# AS726x_Breakout.net
KiCad netlist of a schematic drawn in EAGLE
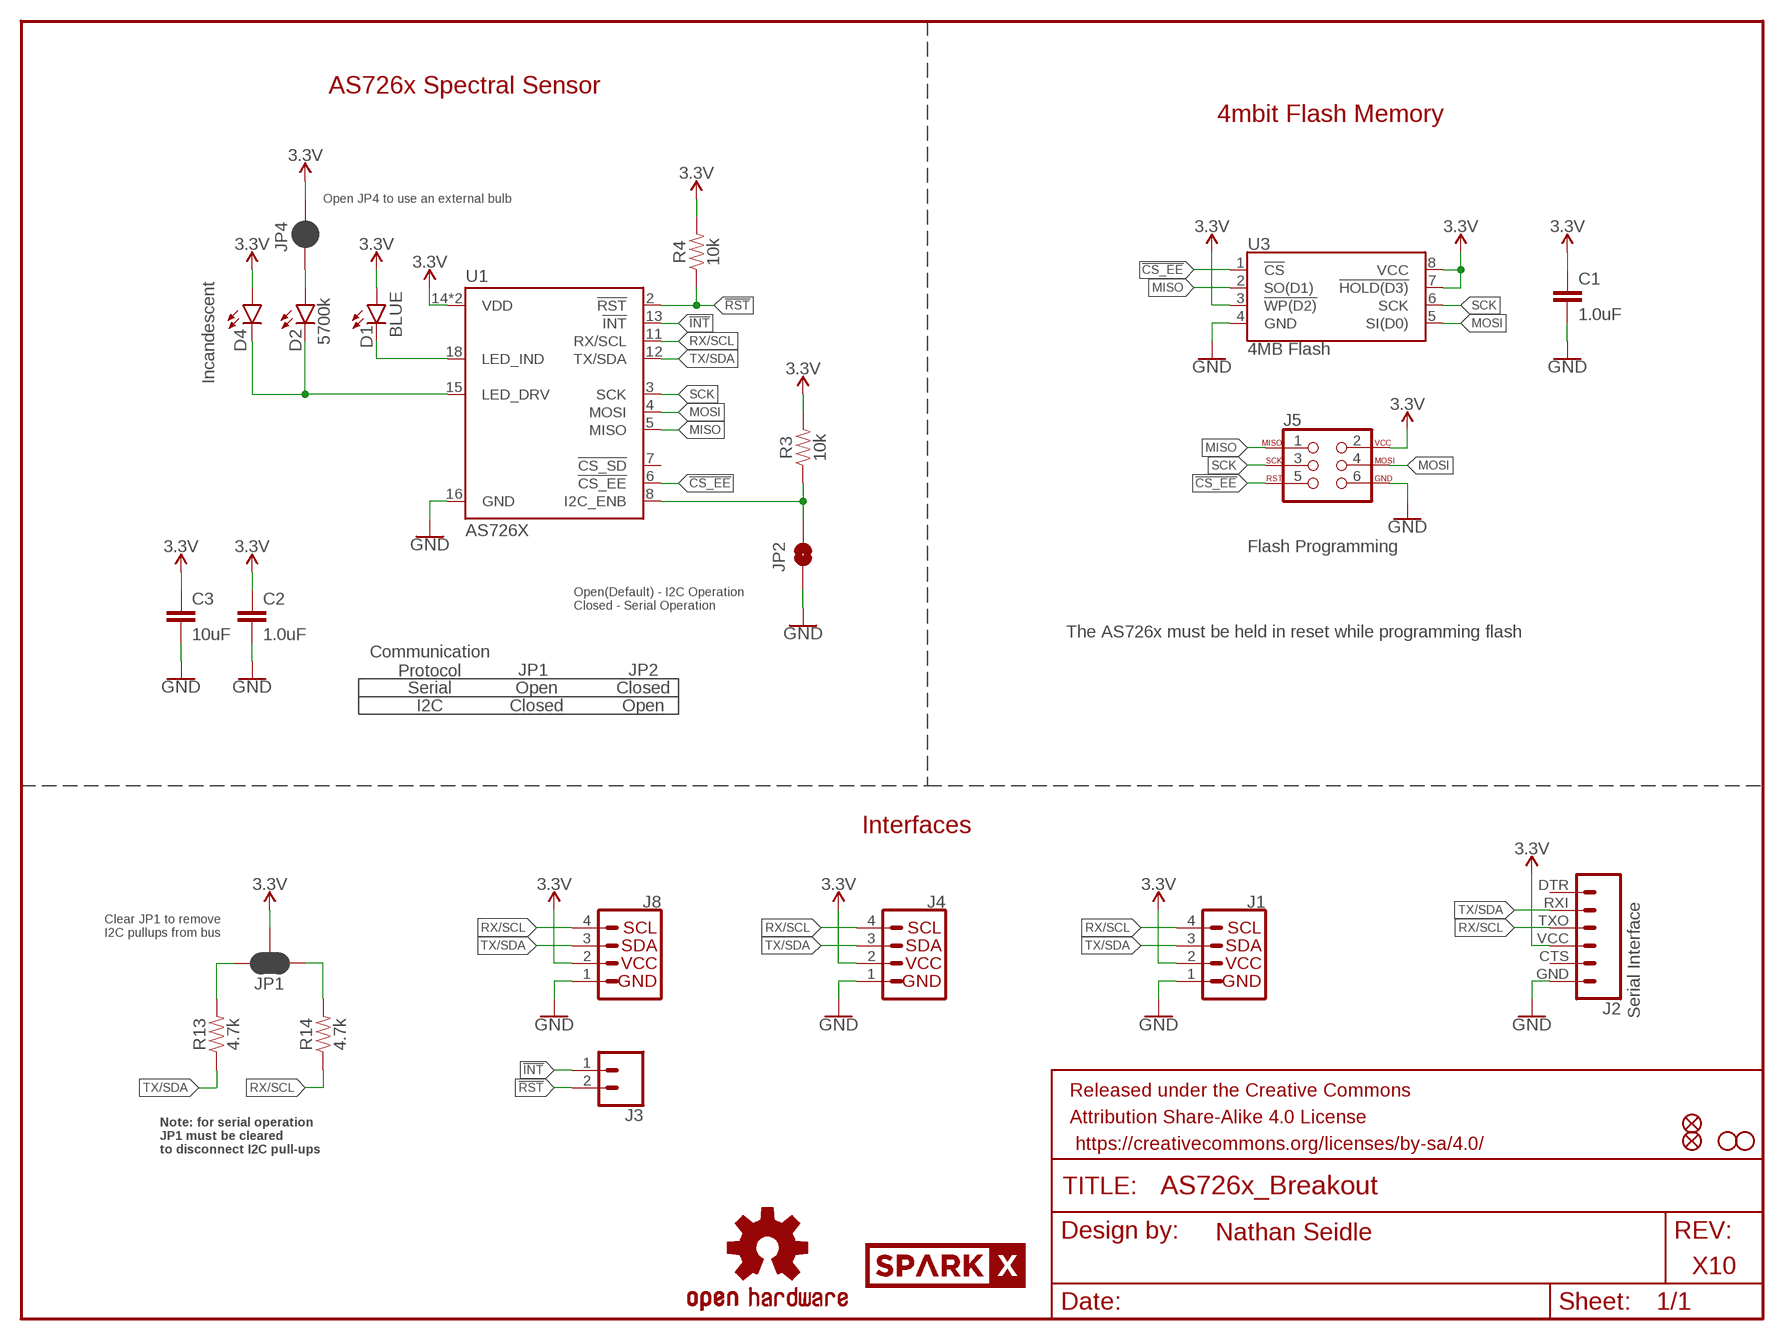
[diagram p0: schematic, sheet 1]

(export (version "E")
  (design (tool "Eeschema 10.0.6"))
  (components
    (comp (ref "C1")
      (value "1.0uF")
      (footprint "eagle-import:0603")
      (libsource (lib "eagle-import") (part "1.0UF-0603-16V-10%"))
    )
    (comp (ref "C2")
      (value "1.0uF")
      (footprint "eagle-import:0603")
      (libsource (lib "eagle-import") (part "1.0UF-0603-16V-10%"))
    )
    (comp (ref "C3")
      (value "10uF")
      (footprint "eagle-import:0603")
      (libsource (lib "eagle-import") (part "10UF-0603-6.3V-20%"))
    )
    (comp (ref "D1")
      (value "BLUE")
      (footprint "eagle-import:LED-0603")
      (libsource (lib "eagle-import") (part "LED-BLUE0603"))
    )
    (comp (ref "D2")
      (value "5700k")
      (footprint "eagle-import:SUPER_BRIGHT_SMD_LED_1206")
      (libsource (lib "eagle-import") (part "LEDLD"))
    )
    (comp (ref "D4")
      (value "Incandescent")
      (footprint "eagle-import:LED_5MM_NOSILK")
      (libsource (lib "eagle-import") (part "LEDNS"))
    )
    (comp (ref "FD1")
      (value "FIDUCIAL1X2")
      (footprint "eagle-import:FIDUCIAL-1X2")
      (libsource (lib "eagle-import") (part "FIDUCIAL1X2"))
    )
    (comp (ref "FD2")
      (value "FIDUCIAL1X2")
      (footprint "eagle-import:FIDUCIAL-1X2")
      (libsource (lib "eagle-import") (part "FIDUCIAL1X2"))
    )
    (comp (ref "FRAME1")
      (value "FRAME-LETTER")
      (footprint "eagle-import:CREATIVE_COMMONS")
      (libsource (lib "eagle-import") (part "FRAME-LETTER"))
    )
    (comp (ref "H2")
      (value "STAND-OFF")
      (footprint "eagle-import:STAND-OFF")
      (libsource (lib "eagle-import") (part "STAND-OFF"))
    )
    (comp (ref "H4")
      (value "STAND-OFF")
      (footprint "eagle-import:STAND-OFF")
      (libsource (lib "eagle-import") (part "STAND-OFF"))
    )
    (comp (ref "J1")
      (value "I2C_STANDARDJS-1MM")
      (footprint "eagle-import:1X04_1MM_RA")
      (libsource (lib "eagle-import") (part "I2C_STANDARDJS-1MM"))
    )
    (comp (ref "J2")
      (value "Serial Interface")
      (footprint "eagle-import:FTDI_BASIC")
      (libsource (lib "eagle-import") (part "6_PIN_SERIAL_CABLEPTH"))
    )
    (comp (ref "J3")
      (value "CONN_021X02_NO_SILK")
      (footprint "eagle-import:1X02_NO_SILK")
      (libsource (lib "eagle-import") (part "CONN_021X02_NO_SILK"))
    )
    (comp (ref "J4")
      (value "I2C_STANDARDJS-1MM")
      (footprint "eagle-import:1X04_1MM_RA")
      (libsource (lib "eagle-import") (part "I2C_STANDARDJS-1MM"))
    )
    (comp (ref "J5")
      (value "Flash Programming")
      (footprint "eagle-import:2X3_TEST_POINTS")
      (libsource (lib "eagle-import") (part "AVR_SPI_PROG_3X2TESTPOINTS"))
    )
    (comp (ref "J8")
      (value "I2C_STANDARD_NO_SILK")
      (footprint "eagle-import:1X04_NO_SILK")
      (libsource (lib "eagle-import") (part "I2C_STANDARD_NO_SILK"))
    )
    (comp (ref "JP1")
      (value "JUMPER-SMT_3_2-NC_PASTE_SILK")
      (footprint "eagle-import:SMT-JUMPER_3_2-NC_PASTE_SILK")
      (libsource (lib "eagle-import") (part "JUMPER-SMT_3_2-NC_PASTE_SILK"))
    )
    (comp (ref "JP2")
      (value "JUMPER-SMT_2_NO_SILK")
      (footprint "eagle-import:SMT-JUMPER_2_NO_SILK")
      (libsource (lib "eagle-import") (part "JUMPER-SMT_2_NO_SILK"))
    )
    (comp (ref "JP4")
      (value "JUMPER-SMT_2_NC_PASTE_NO-SILK")
      (footprint "eagle-import:SMT-JUMPER_2_NC_PASTE_NO-SILK")
      (libsource (lib "eagle-import") (part "JUMPER-SMT_2_NC_PASTE_NO-SILK"))
    )
    (comp (ref "LOGO4")
      (value "OSHW-LOGOS")
      (footprint "eagle-import:OSHW-LOGO-S")
      (libsource (lib "eagle-import") (part "OSHW-LOGOS"))
    )
    (comp (ref "R3")
      (value "10k")
      (footprint "eagle-import:0603")
      (libsource (lib "eagle-import") (part "10KOHM-0603-1/10W-1%"))
    )
    (comp (ref "R4")
      (value "10k")
      (footprint "eagle-import:0603")
      (libsource (lib "eagle-import") (part "10KOHM-0603-1/10W-1%"))
    )
    (comp (ref "R13")
      (value "4.7k")
      (footprint "eagle-import:0603")
      (libsource (lib "eagle-import") (part "4.7KOHM-0603-1/10W-1%"))
    )
    (comp (ref "R14")
      (value "4.7k")
      (footprint "eagle-import:0603")
      (libsource (lib "eagle-import") (part "4.7KOHM-0603-1/10W-1%"))
    )
    (comp (ref "U$1")
      (value "SPARKX-LOGO3")
      (footprint "eagle-import:SPARKX-SMALL")
      (libsource (lib "eagle-import") (part "SPARKX-LOGO3"))
    )
    (comp (ref "U1")
      (value "AS726X")
      (footprint "eagle-import:LGA20")
      (libsource (lib "eagle-import") (part "AS726X"))
    )
    (comp (ref "U3")
      (value "4MB Flash")
      (footprint "eagle-import:SO08")
      (libsource (lib "eagle-import") (part "AT25SF041"))
    )
  )
  (nets
    (net (code "1") (name "/~{CS_EE}") (class "Default")
      (node (ref "J5") (pin "5") (pinfunction "5_5") (pintype "passive"))
      (node (ref "U1") (pin "6") (pinfunction "~{CS_EE}_6") (pintype "bidirectional"))
      (node (ref "U3") (pin "1") (pinfunction "~{CS}_1") (pintype "bidirectional"))
    )
    (net (code "2") (name "/~{INT}") (class "Default")
      (node (ref "J3") (pin "1") (pinfunction "1_1") (pintype "passive"))
      (node (ref "U1") (pin "13") (pinfunction "~{INT}_13") (pintype "bidirectional"))
    )
    (net (code "3") (name "/~{RST}") (class "Default")
      (node (ref "J3") (pin "2") (pinfunction "2_2") (pintype "passive"))
      (node (ref "R4") (pin "1") (pinfunction "1_1") (pintype "passive"))
      (node (ref "U1") (pin "2") (pinfunction "~{RST}_2") (pintype "bidirectional"))
    )
    (net (code "4") (name "3.3V") (class "Default")
      (node (ref "C1") (pin "1") (pinfunction "1_1") (pintype "passive"))
      (node (ref "C2") (pin "1") (pinfunction "1_1") (pintype "passive"))
      (node (ref "C3") (pin "1") (pinfunction "1_1") (pintype "passive"))
      (node (ref "D1") (pin "A") (pinfunction "A_A") (pintype "passive"))
      (node (ref "D4") (pin "A") (pinfunction "A_A") (pintype "passive"))
      (node (ref "J1") (pin "2") (pinfunction "VCC_2") (pintype "power_in"))
      (node (ref "J2") (pin "VCC") (pinfunction "4_VCC") (pintype "passive"))
      (node (ref "J4") (pin "2") (pinfunction "VCC_2") (pintype "power_in"))
      (node (ref "J5") (pin "2") (pinfunction "2_2") (pintype "passive"))
      (node (ref "J8") (pin "2") (pinfunction "2_2") (pintype "power_in"))
      (node (ref "JP1") (pin "2") (pinfunction "2_2") (pintype "passive"))
      (node (ref "JP4") (pin "2") (pinfunction "2_2") (pintype "passive"))
      (node (ref "R3") (pin "2") (pinfunction "2_2") (pintype "passive"))
      (node (ref "R4") (pin "2") (pinfunction "2_2") (pintype "passive"))
      (node (ref "U1") (pin "14") (pinfunction "VDD_14") (pintype "bidirectional"))
      (node (ref "U1") (pin "17") (pinfunction "VDD_17") (pintype "bidirectional"))
      (node (ref "U3") (pin "3") (pinfunction "~{WP(D2})_3") (pintype "bidirectional"))
      (node (ref "U3") (pin "7") (pinfunction "~{HOLD(D3})_7") (pintype "bidirectional"))
      (node (ref "U3") (pin "8") (pinfunction "VCC_8") (pintype "bidirectional"))
    )
    (net (code "5") (name "GND") (class "Default")
      (node (ref "C1") (pin "2") (pinfunction "2_2") (pintype "passive"))
      (node (ref "C2") (pin "2") (pinfunction "2_2") (pintype "passive"))
      (node (ref "C3") (pin "2") (pinfunction "2_2") (pintype "passive"))
      (node (ref "J1") (pin "1") (pinfunction "GND_1") (pintype "power_in"))
      (node (ref "J2") (pin "GND") (pinfunction "6_GND") (pintype "passive"))
      (node (ref "J4") (pin "1") (pinfunction "GND_1") (pintype "power_in"))
      (node (ref "J5") (pin "6") (pinfunction "6_6") (pintype "passive"))
      (node (ref "J8") (pin "1") (pinfunction "1_1") (pintype "power_in"))
      (node (ref "JP2") (pin "1") (pinfunction "1_1") (pintype "passive"))
      (node (ref "U1") (pin "16") (pinfunction "GND_16") (pintype "bidirectional"))
      (node (ref "U3") (pin "4") (pinfunction "GND_4") (pintype "bidirectional"))
    )
    (net (code "6") (name "MISO") (class "Default")
      (node (ref "J5") (pin "1") (pinfunction "1_1") (pintype "passive"))
      (node (ref "U1") (pin "5") (pinfunction "MISO_5") (pintype "bidirectional"))
      (node (ref "U3") (pin "2") (pinfunction "SO(D1)_2") (pintype "bidirectional"))
    )
    (net (code "7") (name "MOSI") (class "Default")
      (node (ref "J5") (pin "4") (pinfunction "4_4") (pintype "passive"))
      (node (ref "U1") (pin "4") (pinfunction "MOSI_4") (pintype "bidirectional"))
      (node (ref "U3") (pin "5") (pinfunction "SI(D0)_5") (pintype "bidirectional"))
    )
    (net (code "8") (name "Net-(D2-PadA)") (class "Default")
      (node (ref "D2") (pin "A") (pinfunction "A_A") (pintype "passive"))
      (node (ref "JP4") (pin "1") (pinfunction "1_1") (pintype "passive"))
    )
    (net (code "9") (name "Net-(D4-C)") (class "Default")
      (node (ref "D2") (pin "C") (pinfunction "C_C") (pintype "passive"))
      (node (ref "D4") (pin "K") (pinfunction "C_K") (pintype "passive"))
      (node (ref "U1") (pin "15") (pinfunction "LED_DRV_15") (pintype "bidirectional"))
    )
    (net (code "10") (name "Net-(JP1-Pad1)") (class "Default")
      (node (ref "JP1") (pin "1") (pinfunction "1_1") (pintype "passive"))
      (node (ref "R14") (pin "2") (pinfunction "2_2") (pintype "passive"))
    )
    (net (code "11") (name "Net-(JP1-Pad3)") (class "Default")
      (node (ref "JP1") (pin "3") (pinfunction "3_3") (pintype "passive"))
      (node (ref "R13") (pin "2") (pinfunction "2_2") (pintype "passive"))
    )
    (net (code "12") (name "Net-(U1-I2C_ENB)") (class "Default")
      (node (ref "JP2") (pin "2") (pinfunction "2_2") (pintype "passive"))
      (node (ref "R3") (pin "1") (pinfunction "1_1") (pintype "passive"))
      (node (ref "U1") (pin "8") (pinfunction "I2C_ENB_8") (pintype "bidirectional"))
    )
    (net (code "13") (name "Net-(U1-LED_IND)") (class "Default")
      (node (ref "D1") (pin "C") (pinfunction "C_C") (pintype "passive"))
      (node (ref "U1") (pin "18") (pinfunction "LED_IND_18") (pintype "bidirectional"))
    )
    (net (code "14") (name "RX{slash}SCL") (class "Default")
      (node (ref "J1") (pin "4") (pinfunction "SCL_4") (pintype "passive"))
      (node (ref "J2") (pin "TXO") (pinfunction "3_TXO") (pintype "passive"))
      (node (ref "J4") (pin "4") (pinfunction "SCL_4") (pintype "passive"))
      (node (ref "J8") (pin "4") (pinfunction "4_4") (pintype "passive"))
      (node (ref "R14") (pin "1") (pinfunction "1_1") (pintype "passive"))
      (node (ref "U1") (pin "11") (pinfunction "RX/SCL_11") (pintype "bidirectional"))
    )
    (net (code "15") (name "SCK") (class "Default")
      (node (ref "J5") (pin "3") (pinfunction "3_3") (pintype "passive"))
      (node (ref "U1") (pin "3") (pinfunction "SCK_3") (pintype "bidirectional"))
      (node (ref "U3") (pin "6") (pinfunction "SCK_6") (pintype "bidirectional"))
    )
    (net (code "16") (name "TX{slash}SDA") (class "Default")
      (node (ref "J1") (pin "3") (pinfunction "SDA_3") (pintype "passive"))
      (node (ref "J2") (pin "RXI") (pinfunction "2_RXI") (pintype "passive"))
      (node (ref "J4") (pin "3") (pinfunction "SDA_3") (pintype "passive"))
      (node (ref "J8") (pin "3") (pinfunction "3_3") (pintype "passive"))
      (node (ref "R13") (pin "1") (pinfunction "1_1") (pintype "passive"))
      (node (ref "U1") (pin "12") (pinfunction "TX/SDA_12") (pintype "bidirectional"))
    )
    (net (code "17") (name "unconnected-(J2-1-PadDTR)") (class "Default")
      (node (ref "J2") (pin "DTR") (pinfunction "1_DTR") (pintype "passive"))
    )
    (net (code "18") (name "unconnected-(J2-5-PadCTS)") (class "Default")
      (node (ref "J2") (pin "CTS") (pinfunction "5_CTS") (pintype "passive"))
    )
    (net (code "19") (name "unconnected-(U1-~{CS_SD}-Pad7)") (class "Default")
      (node (ref "U1") (pin "7") (pinfunction "~{CS_SD}_7") (pintype "bidirectional"))
    )
  )
)
